# ZUM_Core_Autoreset.net
KiCad netlist of a schematic drawn in Altium Designer
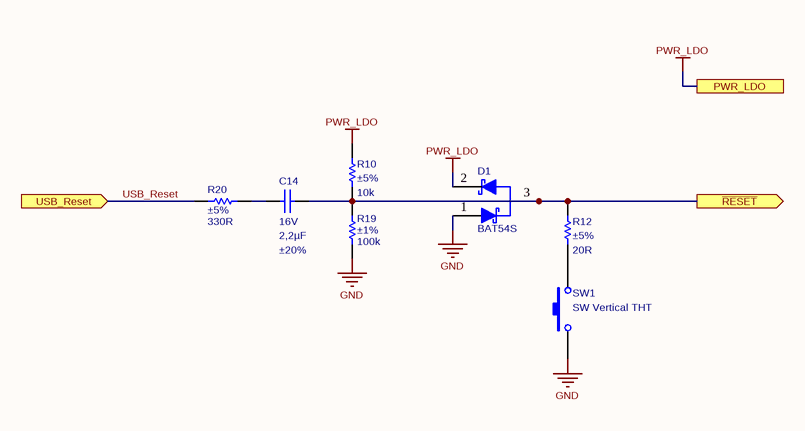
[diagram p0: ZUM_Core_Autoreset.SchDoc]

(export (version "E")
  (design (tool "Eeschema 10.0.6"))
  (components
    (comp (ref "C14")
      (value "C0402_2.2uF_16V_±20%")
      (footprint "C0402")
      (description "C0402_2.2uF_16V_±20%_X5R")
      (fields
        (field (name "VOLTAGE") "16V")
        (field (name "CAPACITANCE") "2,2µF")
        (field (name "PART NUMBER") "C0402_2.2uF_16V_±10%")
        (field (name "TOLERANCE") "±20%")
        (field (name "MANUFACTURER") "TDK")
      )
      (libsource (lib "BQ Vault") (part "Capacitor"))
    )
    (comp (ref "D1")
      (value "BAT54S")
      (footprint "SOT23-3")
      (description "Schottky Diode")
      (fields (field (name "MANUFACTURER") "NXP"))
      (libsource (lib "BQ Vault") (part "CMP-A2299-1"))
    )
    (comp (ref "R10")
      (value "R0402_10k_0.063W_±5%")
      (footprint "R0402")
      (fields
        (field (name "TOLERANCE") "±5%")
        (field (name "POWER") "0.063W")
        (field (name "RESISTANCE") "10k")
        (field (name "MANUFACTURER") "Vishay")
      )
      (libsource (lib "BQ Vault") (part "CMP-A1692-4"))
    )
    (comp (ref "R12")
      (value "R0402_20R_0.063W_±5%")
      (footprint "R0402")
      (fields
        (field (name "TOLERANCE") "±5%")
        (field (name "POWER") "0.063W")
        (field (name "RESISTANCE") "20R")
        (field (name "MANUFACTURER") "Vishay")
      )
      (libsource (lib "BQ Vault") (part "Resistor"))
    )
    (comp (ref "R19")
      (value "R0402_100k_0.063W_±1%")
      (footprint "R0402")
      (fields
        (field (name "TOLERANCE") "±1%")
        (field (name "POWER") "0.063W")
        (field (name "RESISTANCE") "100k")
        (field (name "MANUFACTURER") "Vishay")
      )
      (libsource (lib "BQ Vault") (part "Resistor"))
    )
    (comp (ref "R20")
      (value "R0402_330R_0.063W_±5%")
      (footprint "R0402")
      (fields
        (field (name "TOLERANCE") "±5%")
        (field (name "POWER") "0.063W")
        (field (name "RESISTANCE") "330R")
        (field (name "MANUFACTURER") "Vishay")
      )
      (libsource (lib "BQ Vault") (part "CMP-A1762-2"))
    )
    (comp (ref "SW1")
      (value "SW Vertical THT")
      (footprint "SW_Vert_THT_7.5x6x6.5")
      (description "Switch")
      (fields (field (name "MANUFACTURER") "C&K Components"))
      (libsource (lib "BQ Vault") (part "Switch"))
    )
  )
  (nets
    (net (code "1") (name "/USB_Reset") (class "Default")
      (node (ref "R20") (pin "2") (pinfunction "2_2") (pintype "passive"))
    )
    (net (code "2") (name "/~{RESET}") (class "Default")
      (node (ref "C14") (pin "1") (pinfunction "1_1") (pintype "passive"))
      (node (ref "D1") (pin "3") (pinfunction "K1_3") (pintype "passive"))
      (node (ref "R10") (pin "2") (pinfunction "2_2") (pintype "passive"))
      (node (ref "R12") (pin "2") (pinfunction "2_2") (pintype "passive"))
      (node (ref "R19") (pin "1") (pinfunction "1_1") (pintype "passive"))
    )
    (net (code "3") (name "GND") (class "Default")
      (node (ref "D1") (pin "1") (pinfunction "A_1") (pintype "passive"))
      (node (ref "R19") (pin "2") (pinfunction "2_2") (pintype "passive"))
      (node (ref "SW1") (pin "1") (pinfunction "1_1") (pintype "passive"))
    )
    (net (code "4") (name "Net-(C14-Pad2)") (class "Default")
      (node (ref "C14") (pin "2") (pinfunction "2_2") (pintype "passive"))
      (node (ref "R20") (pin "1") (pinfunction "1_1") (pintype "passive"))
    )
    (net (code "5") (name "Net-(R12-Pad1)") (class "Default")
      (node (ref "R12") (pin "1") (pinfunction "1_1") (pintype "passive"))
      (node (ref "SW1") (pin "2") (pinfunction "2_2") (pintype "passive"))
    )
    (net (code "6") (name "PWR_LDO") (class "Default")
      (node (ref "D1") (pin "2") (pinfunction "K2_2") (pintype "passive"))
      (node (ref "R10") (pin "1") (pinfunction "1_1") (pintype "passive"))
    )
  )
)
